# Sheet_1_2021-05-21.net
KiCad netlist of a schematic drawn in Altium Designer
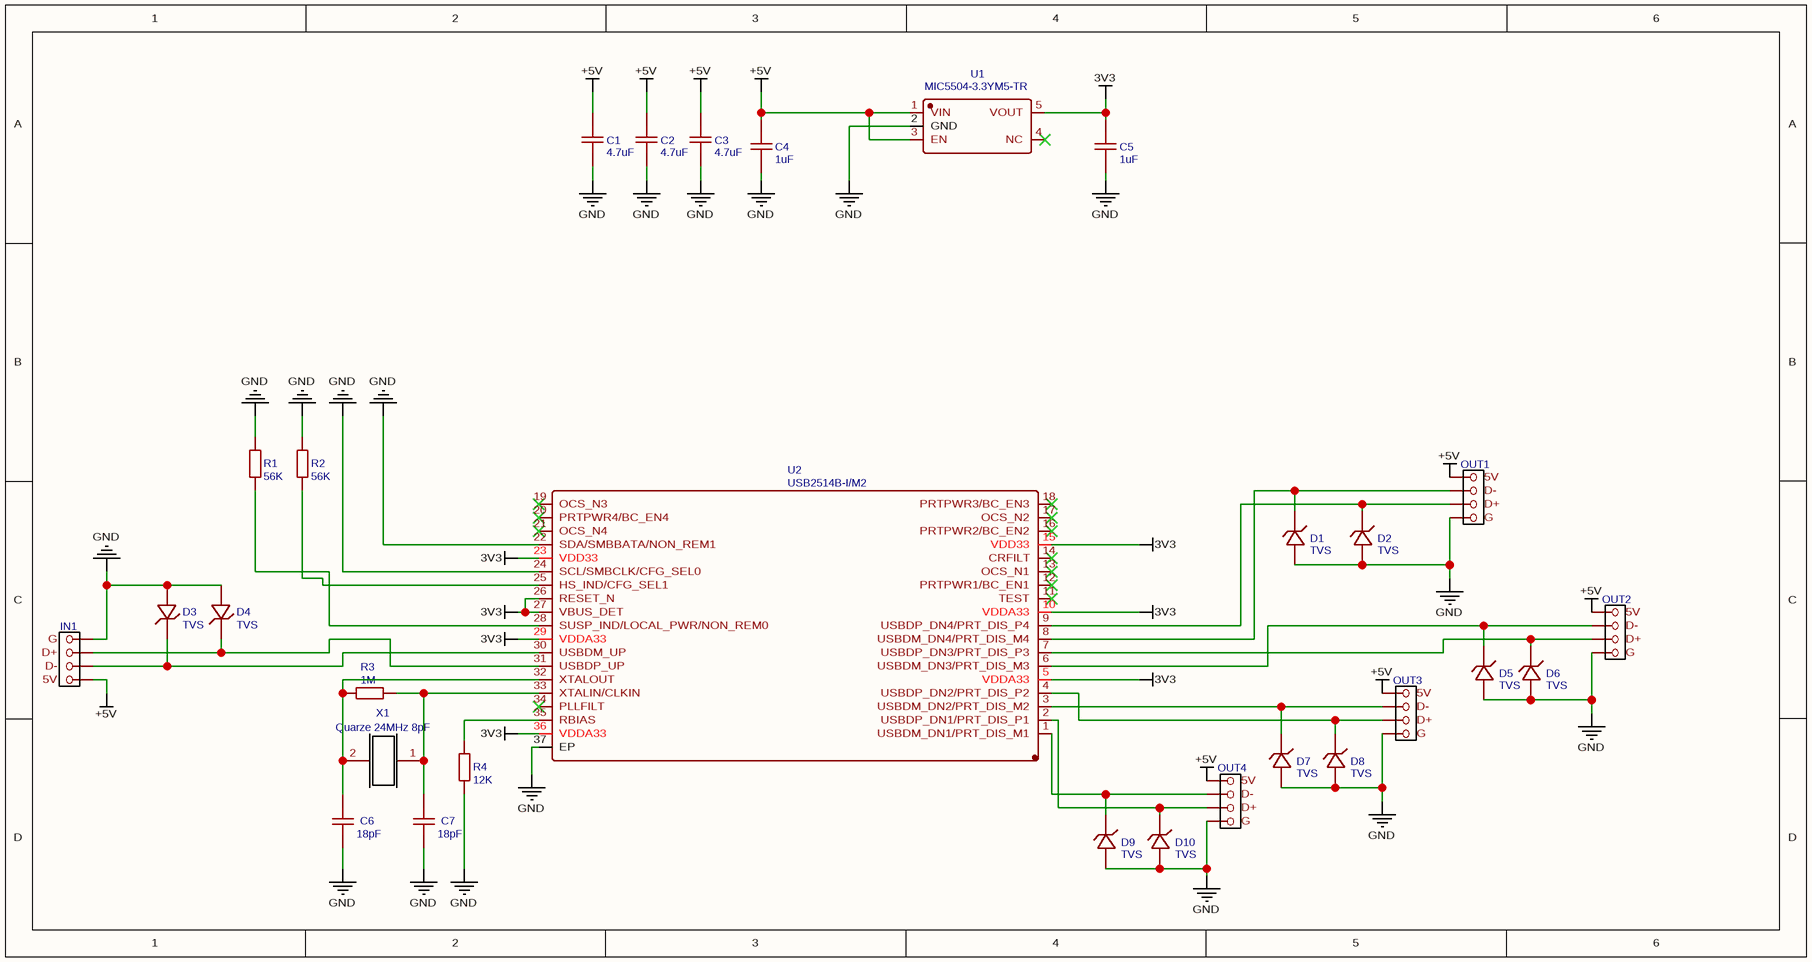
[diagram p0: Sheet_1_2021-05-21.schdoc]

(export (version "E")
  (design (tool "Eeschema 10.0.6"))
  (components
    (comp (ref "C1")
      (value "4.7uF")
      (fields (field (name "BOM_MANUFACTURER PART") "?") (field (name "BOM_SUPPLIER PART") "C1590"))
      (libsource (lib "altium-import") (part "root_3_4.7uF_"))
    )
    (comp (ref "C2")
      (value "4.7uF")
      (fields (field (name "BOM_MANUFACTURER PART") "?") (field (name "BOM_SUPPLIER PART") "C1590"))
      (libsource (lib "altium-import") (part "root_3_4.7uF_"))
    )
    (comp (ref "C3")
      (value "4.7uF")
      (fields (field (name "BOM_MANUFACTURER PART") "?") (field (name "BOM_SUPPLIER PART") "C1590"))
      (libsource (lib "altium-import") (part "root_3_4.7uF_"))
    )
    (comp (ref "C4")
      (value "1uF")
      (fields (field (name "BOM_MANUFACTURER PART") "?") (field (name "BOM_SUPPLIER PART") "C1590"))
      (libsource (lib "altium-import") (part "root_3_1uF_"))
    )
    (comp (ref "C5")
      (value "1uF")
      (fields (field (name "BOM_MANUFACTURER PART") "?") (field (name "BOM_SUPPLIER PART") "C1590"))
      (libsource (lib "altium-import") (part "root_3_1uF_"))
    )
    (comp (ref "C6")
      (value "18pF")
      (fields (field (name "BOM_MANUFACTURER PART") "?") (field (name "BOM_SUPPLIER PART") "C1590"))
      (libsource (lib "altium-import") (part "root_1_18pF_"))
    )
    (comp (ref "C7")
      (value "18pF")
      (fields (field (name "BOM_MANUFACTURER PART") "?") (field (name "BOM_SUPPLIER PART") "C1590"))
      (libsource (lib "altium-import") (part "root_1_18pF_"))
    )
    (comp (ref "D1")
      (value "TVS")
      (fields
        (field (name "BOM_SUPPLIER PART") "C172439")
        (field (name "BOM_MANUFACTURER PART") "LTVS16H12T5G")
        (field (name "CONTRIBUTOR") "LCSC")
      )
      (libsource (lib "altium-import") (part "root_3_TVS_"))
    )
    (comp (ref "D2")
      (value "TVS")
      (fields
        (field (name "BOM_SUPPLIER PART") "C172439")
        (field (name "BOM_MANUFACTURER PART") "LTVS16H12T5G")
        (field (name "CONTRIBUTOR") "LCSC")
      )
      (libsource (lib "altium-import") (part "root_3_TVS_"))
    )
    (comp (ref "D3")
      (value "TVS")
      (fields
        (field (name "BOM_SUPPLIER PART") "C172439")
        (field (name "BOM_MANUFACTURER PART") "LTVS16H12T5G")
        (field (name "CONTRIBUTOR") "LCSC")
      )
      (libsource (lib "altium-import") (part "root_1_TVS_"))
    )
    (comp (ref "D4")
      (value "TVS")
      (fields
        (field (name "BOM_SUPPLIER PART") "C172439")
        (field (name "BOM_MANUFACTURER PART") "LTVS16H12T5G")
        (field (name "CONTRIBUTOR") "LCSC")
      )
      (libsource (lib "altium-import") (part "root_1_TVS_"))
    )
    (comp (ref "D5")
      (value "TVS")
      (fields
        (field (name "BOM_SUPPLIER PART") "C172439")
        (field (name "BOM_MANUFACTURER PART") "LTVS16H12T5G")
        (field (name "CONTRIBUTOR") "LCSC")
      )
      (libsource (lib "altium-import") (part "root_3_TVS_"))
    )
    (comp (ref "D6")
      (value "TVS")
      (fields
        (field (name "BOM_SUPPLIER PART") "C172439")
        (field (name "BOM_MANUFACTURER PART") "LTVS16H12T5G")
        (field (name "CONTRIBUTOR") "LCSC")
      )
      (libsource (lib "altium-import") (part "root_3_TVS_"))
    )
    (comp (ref "D7")
      (value "TVS")
      (fields
        (field (name "BOM_SUPPLIER PART") "C172439")
        (field (name "BOM_MANUFACTURER PART") "LTVS16H12T5G")
        (field (name "CONTRIBUTOR") "LCSC")
      )
      (libsource (lib "altium-import") (part "root_3_TVS_"))
    )
    (comp (ref "D8")
      (value "TVS")
      (fields
        (field (name "BOM_SUPPLIER PART") "C172439")
        (field (name "BOM_MANUFACTURER PART") "LTVS16H12T5G")
        (field (name "CONTRIBUTOR") "LCSC")
      )
      (libsource (lib "altium-import") (part "root_3_TVS_"))
    )
    (comp (ref "D9")
      (value "TVS")
      (fields
        (field (name "BOM_SUPPLIER PART") "C172439")
        (field (name "BOM_MANUFACTURER PART") "LTVS16H12T5G")
        (field (name "CONTRIBUTOR") "LCSC")
      )
      (libsource (lib "altium-import") (part "root_3_TVS_"))
    )
    (comp (ref "D10")
      (value "TVS")
      (fields
        (field (name "BOM_SUPPLIER PART") "C172439")
        (field (name "BOM_MANUFACTURER PART") "LTVS16H12T5G")
        (field (name "CONTRIBUTOR") "LCSC")
      )
      (libsource (lib "altium-import") (part "root_3_TVS_"))
    )
    (comp (ref "IN1")
      (value "EXT-JST")
      (fields (field (name "BOM_MANUFACTURER PART") "XH-4A") (field (name "CONTRIBUTOR") "oliver.mike"))
      (libsource (lib "altium-import") (part "root_1_EXT-JST_"))
    )
    (comp (ref "OUT1")
      (value "EXT-JST")
      (fields (field (name "BOM_MANUFACTURER PART") "XH-4A") (field (name "CONTRIBUTOR") "oliver.mike"))
      (libsource (lib "altium-import") (part "root_3_EXT-JST_"))
    )
    (comp (ref "OUT2")
      (value "EXT-JST")
      (fields (field (name "BOM_MANUFACTURER PART") "XH-4A") (field (name "CONTRIBUTOR") "oliver.mike"))
      (libsource (lib "altium-import") (part "root_3_EXT-JST_"))
    )
    (comp (ref "OUT3")
      (value "EXT-JST")
      (fields (field (name "BOM_MANUFACTURER PART") "XH-4A") (field (name "CONTRIBUTOR") "oliver.mike"))
      (libsource (lib "altium-import") (part "root_3_EXT-JST_"))
    )
    (comp (ref "OUT4")
      (value "EXT-JST")
      (fields (field (name "BOM_MANUFACTURER PART") "XH-4A") (field (name "CONTRIBUTOR") "oliver.mike"))
      (libsource (lib "altium-import") (part "root_3_EXT-JST_"))
    )
    (comp (ref "R1")
      (value "56K")
      (fields (field (name "BOM_MANUFACTURER PART") "?") (field (name "BOM_SUPPLIER PART") "C25585"))
      (libsource (lib "altium-import") (part "root_3_56K_"))
    )
    (comp (ref "R2")
      (value "56K")
      (fields (field (name "BOM_MANUFACTURER PART") "?") (field (name "BOM_SUPPLIER PART") "C25585"))
      (libsource (lib "altium-import") (part "root_3_56K_"))
    )
    (comp (ref "R3")
      (value "1M")
      (fields (field (name "BOM_MANUFACTURER PART") "?") (field (name "BOM_SUPPLIER PART") "C25585"))
      (libsource (lib "altium-import") (part "root_0_1M_"))
    )
    (comp (ref "R4")
      (value "12K")
      (fields (field (name "BOM_MANUFACTURER PART") "?") (field (name "BOM_SUPPLIER PART") "C25585"))
      (libsource (lib "altium-import") (part "root_3_12K_"))
    )
    (comp (ref "U1")
      (value "MIC5504-3.3YM5-TR")
      (fields (field (name "BOM_SUPPLIER PART") "C88419") (field (name "CONTRIBUTOR") "LCSC"))
      (libsource (lib "altium-import") (part "root_0_MIC5504-3.3YM5-TR_"))
    )
    (comp (ref "U2")
      (value "USB2514B-I/M2")
      (fields (field (name "BOM_SUPPLIER PART") "C220679") (field (name "CONTRIBUTOR") "LCSC"))
      (libsource (lib "altium-import") (part "root_2_USB2514B-I/M2_"))
    )
    (comp (ref "X1")
      (value "Quarze 24MHz 8pF")
      (fields
        (field (name "BOM_MANUFACTURER PART") "ABM10W-24.0000MHZ-8-D1X-T3")
        (field (name "BOM_SUPPLIER PART") "815-10W24-8D1XT")
        (field (name "CONTRIBUTOR") "lalufani")
      )
      (libsource (lib "altium-import") (part "root_2_Quarze 24MHz 8pF_"))
    )
  )
  (nets
    (net (code "1") (name "+5V") (class "Default")
      (node (ref "C1") (pin "1") (pinfunction "1_1") (pintype "passive"))
      (node (ref "C2") (pin "1") (pinfunction "1_1") (pintype "passive"))
      (node (ref "C3") (pin "1") (pinfunction "1_1") (pintype "passive"))
      (node (ref "C4") (pin "1") (pinfunction "1_1") (pintype "passive"))
      (node (ref "IN1") (pin "1") (pinfunction "5V_1") (pintype "passive"))
      (node (ref "OUT1") (pin "1") (pinfunction "5V_1") (pintype "passive"))
      (node (ref "OUT2") (pin "1") (pinfunction "5V_1") (pintype "passive"))
      (node (ref "OUT3") (pin "1") (pinfunction "5V_1") (pintype "passive"))
      (node (ref "OUT4") (pin "1") (pinfunction "5V_1") (pintype "passive"))
      (node (ref "U1") (pin "1") (pinfunction "VIN_1") (pintype "passive"))
      (node (ref "U1") (pin "3") (pinfunction "EN_3") (pintype "passive"))
    )
    (net (code "2") (name "3V3") (class "Default")
      (node (ref "C5") (pin "1") (pinfunction "1_1") (pintype "passive"))
      (node (ref "U1") (pin "5") (pinfunction "VOUT_5") (pintype "passive"))
      (node (ref "U2") (pin "10") (pinfunction "VDDA33_10") (pintype "passive"))
      (node (ref "U2") (pin "15") (pinfunction "VDD33_15") (pintype "passive"))
      (node (ref "U2") (pin "23") (pinfunction "VDD33_23") (pintype "passive"))
      (node (ref "U2") (pin "26") (pinfunction "RESET_N_26") (pintype "passive"))
      (node (ref "U2") (pin "27") (pinfunction "VBUS_DET_27") (pintype "passive"))
      (node (ref "U2") (pin "29") (pinfunction "VDDA33_29") (pintype "passive"))
      (node (ref "U2") (pin "36") (pinfunction "VDDA33_36") (pintype "passive"))
      (node (ref "U2") (pin "5") (pinfunction "VDDA33_5") (pintype "passive"))
    )
    (net (code "3") (name "GND") (class "Default")
      (node (ref "C1") (pin "2") (pinfunction "2_2") (pintype "passive"))
      (node (ref "C2") (pin "2") (pinfunction "2_2") (pintype "passive"))
      (node (ref "C3") (pin "2") (pinfunction "2_2") (pintype "passive"))
      (node (ref "C4") (pin "2") (pinfunction "2_2") (pintype "passive"))
      (node (ref "C5") (pin "2") (pinfunction "2_2") (pintype "passive"))
      (node (ref "C6") (pin "1") (pinfunction "1_1") (pintype "passive"))
      (node (ref "C7") (pin "1") (pinfunction "1_1") (pintype "passive"))
      (node (ref "D1") (pin "2") (pinfunction "2_2") (pintype "passive"))
      (node (ref "D10") (pin "2") (pinfunction "2_2") (pintype "passive"))
      (node (ref "D2") (pin "2") (pinfunction "2_2") (pintype "passive"))
      (node (ref "D3") (pin "2") (pinfunction "2_2") (pintype "passive"))
      (node (ref "D4") (pin "2") (pinfunction "2_2") (pintype "passive"))
      (node (ref "D5") (pin "2") (pinfunction "2_2") (pintype "passive"))
      (node (ref "D6") (pin "2") (pinfunction "2_2") (pintype "passive"))
      (node (ref "D7") (pin "2") (pinfunction "2_2") (pintype "passive"))
      (node (ref "D8") (pin "2") (pinfunction "2_2") (pintype "passive"))
      (node (ref "D9") (pin "2") (pinfunction "2_2") (pintype "passive"))
      (node (ref "IN1") (pin "4") (pinfunction "G_4") (pintype "passive"))
      (node (ref "OUT1") (pin "4") (pinfunction "G_4") (pintype "passive"))
      (node (ref "OUT2") (pin "4") (pinfunction "G_4") (pintype "passive"))
      (node (ref "OUT3") (pin "4") (pinfunction "G_4") (pintype "passive"))
      (node (ref "OUT4") (pin "4") (pinfunction "G_4") (pintype "passive"))
      (node (ref "R1") (pin "1") (pinfunction "1_1") (pintype "passive"))
      (node (ref "R2") (pin "1") (pinfunction "1_1") (pintype "passive"))
      (node (ref "R4") (pin "2") (pinfunction "2_2") (pintype "passive"))
      (node (ref "U1") (pin "2") (pinfunction "GND_2") (pintype "passive"))
      (node (ref "U2") (pin "22") (pinfunction "SDA/SMBBATA/NON_REM1_22") (pintype "passive"))
      (node (ref "U2") (pin "24") (pinfunction "SCL/SMBCLK/CFG_SEL0_24") (pintype "passive"))
      (node (ref "U2") (pin "37") (pinfunction "EP_37") (pintype "passive"))
    )
    (net (code "4") (name "Net-(IN1-D+)") (class "Default")
      (node (ref "D4") (pin "1") (pinfunction "1_1") (pintype "passive"))
      (node (ref "IN1") (pin "3") (pinfunction "D+_3") (pintype "passive"))
      (node (ref "U2") (pin "31") (pinfunction "USBDP_UP_31") (pintype "passive"))
    )
    (net (code "5") (name "Net-(IN1-D-)") (class "Default")
      (node (ref "D3") (pin "1") (pinfunction "1_1") (pintype "passive"))
      (node (ref "IN1") (pin "2") (pinfunction "D-_2") (pintype "passive"))
      (node (ref "U2") (pin "30") (pinfunction "USBDM_UP_30") (pintype "passive"))
    )
    (net (code "6") (name "Net-(OUT1-D+)") (class "Default")
      (node (ref "D2") (pin "1") (pinfunction "1_1") (pintype "passive"))
      (node (ref "OUT1") (pin "3") (pinfunction "D+_3") (pintype "passive"))
      (node (ref "U2") (pin "9") (pinfunction "USBDP_DN4/PRT_DIS_P4_9") (pintype "passive"))
    )
    (net (code "7") (name "Net-(OUT1-D-)") (class "Default")
      (node (ref "D1") (pin "1") (pinfunction "1_1") (pintype "passive"))
      (node (ref "OUT1") (pin "2") (pinfunction "D-_2") (pintype "passive"))
      (node (ref "U2") (pin "8") (pinfunction "USBDM_DN4/PRT_DIS_M4_8") (pintype "passive"))
    )
    (net (code "8") (name "Net-(OUT2-D+)") (class "Default")
      (node (ref "D6") (pin "1") (pinfunction "1_1") (pintype "passive"))
      (node (ref "OUT2") (pin "3") (pinfunction "D+_3") (pintype "passive"))
      (node (ref "U2") (pin "7") (pinfunction "USBDP_DN3/PRT_DIS_P3_7") (pintype "passive"))
    )
    (net (code "9") (name "Net-(OUT2-D-)") (class "Default")
      (node (ref "D5") (pin "1") (pinfunction "1_1") (pintype "passive"))
      (node (ref "OUT2") (pin "2") (pinfunction "D-_2") (pintype "passive"))
      (node (ref "U2") (pin "6") (pinfunction "USBDM_DN3/PRT_DIS_M3_6") (pintype "passive"))
    )
    (net (code "10") (name "Net-(OUT3-D+)") (class "Default")
      (node (ref "D8") (pin "1") (pinfunction "1_1") (pintype "passive"))
      (node (ref "OUT3") (pin "3") (pinfunction "D+_3") (pintype "passive"))
      (node (ref "U2") (pin "4") (pinfunction "USBDP_DN2/PRT_DIS_P2_4") (pintype "passive"))
    )
    (net (code "11") (name "Net-(OUT3-D-)") (class "Default")
      (node (ref "D7") (pin "1") (pinfunction "1_1") (pintype "passive"))
      (node (ref "OUT3") (pin "2") (pinfunction "D-_2") (pintype "passive"))
      (node (ref "U2") (pin "3") (pinfunction "USBDM_DN2/PRT_DIS_M2_3") (pintype "passive"))
    )
    (net (code "12") (name "Net-(OUT4-D+)") (class "Default")
      (node (ref "D10") (pin "1") (pinfunction "1_1") (pintype "passive"))
      (node (ref "OUT4") (pin "3") (pinfunction "D+_3") (pintype "passive"))
      (node (ref "U2") (pin "2") (pinfunction "USBDP_DN1/PRT_DIS_P1_2") (pintype "passive"))
    )
    (net (code "13") (name "Net-(OUT4-D-)") (class "Default")
      (node (ref "D9") (pin "1") (pinfunction "1_1") (pintype "passive"))
      (node (ref "OUT4") (pin "2") (pinfunction "D-_2") (pintype "passive"))
      (node (ref "U2") (pin "1") (pinfunction "USBDM_DN1/PRT_DIS_M1_1") (pintype "passive"))
    )
    (net (code "14") (name "Net-(U2-HS_IND{slash}CFG_SEL1)") (class "Default")
      (node (ref "R2") (pin "2") (pinfunction "2_2") (pintype "passive"))
      (node (ref "U2") (pin "25") (pinfunction "HS_IND/CFG_SEL1_25") (pintype "passive"))
    )
    (net (code "15") (name "Net-(U2-RBIAS)") (class "Default")
      (node (ref "R4") (pin "1") (pinfunction "1_1") (pintype "passive"))
      (node (ref "U2") (pin "35") (pinfunction "RBIAS_35") (pintype "passive"))
    )
    (net (code "16") (name "Net-(U2-SUSP_IND{slash}LOCAL_PWR{slash}NON_REM0)") (class "Default")
      (node (ref "R1") (pin "2") (pinfunction "2_2") (pintype "passive"))
      (node (ref "U2") (pin "28") (pinfunction "SUSP_IND/LOCAL_PWR/NON_REM0_28") (pintype "passive"))
    )
    (net (code "17") (name "Net-(U2-XTALIN{slash}CLKIN)") (class "Default")
      (node (ref "C7") (pin "2") (pinfunction "2_2") (pintype "passive"))
      (node (ref "R3") (pin "2") (pinfunction "2_2") (pintype "passive"))
      (node (ref "U2") (pin "33") (pinfunction "XTALIN/CLKIN_33") (pintype "passive"))
      (node (ref "X1") (pin "1") (pinfunction "1_1") (pintype "passive"))
    )
    (net (code "18") (name "Net-(U2-XTALOUT)") (class "Default")
      (node (ref "C6") (pin "2") (pinfunction "2_2") (pintype "passive"))
      (node (ref "R3") (pin "1") (pinfunction "1_1") (pintype "passive"))
      (node (ref "U2") (pin "32") (pinfunction "XTALOUT_32") (pintype "passive"))
      (node (ref "X1") (pin "2") (pinfunction "2_2") (pintype "passive"))
    )
    (net (code "19") (name "unconnected-(U1-NC-Pad4)") (class "Default")
      (node (ref "U1") (pin "4") (pinfunction "NC_4") (pintype "passive+no_connect"))
    )
    (net (code "20") (name "unconnected-(U2-CRFILT-Pad14)") (class "Default")
      (node (ref "U2") (pin "14") (pinfunction "CRFILT_14") (pintype "passive+no_connect"))
    )
    (net (code "21") (name "unconnected-(U2-OCS_N1-Pad13)") (class "Default")
      (node (ref "U2") (pin "13") (pinfunction "OCS_N1_13") (pintype "passive+no_connect"))
    )
    (net (code "22") (name "unconnected-(U2-OCS_N2-Pad17)") (class "Default")
      (node (ref "U2") (pin "17") (pinfunction "OCS_N2_17") (pintype "passive+no_connect"))
    )
    (net (code "23") (name "unconnected-(U2-OCS_N3-Pad19)") (class "Default")
      (node (ref "U2") (pin "19") (pinfunction "OCS_N3_19") (pintype "passive+no_connect"))
    )
    (net (code "24") (name "unconnected-(U2-OCS_N4-Pad21)") (class "Default")
      (node (ref "U2") (pin "21") (pinfunction "OCS_N4_21") (pintype "passive+no_connect"))
    )
    (net (code "25") (name "unconnected-(U2-PLLFILT-Pad34)") (class "Default")
      (node (ref "U2") (pin "34") (pinfunction "PLLFILT_34") (pintype "passive+no_connect"))
    )
    (net (code "26") (name "unconnected-(U2-PRTPWR1{slash}BC_EN1-Pad12)") (class "Default")
      (node (ref "U2") (pin "12") (pinfunction "PRTPWR1/BC_EN1_12") (pintype "passive+no_connect"))
    )
    (net (code "27") (name "unconnected-(U2-PRTPWR2{slash}BC_EN2-Pad16)") (class "Default")
      (node (ref "U2") (pin "16") (pinfunction "PRTPWR2/BC_EN2_16") (pintype "passive+no_connect"))
    )
    (net (code "28") (name "unconnected-(U2-PRTPWR3{slash}BC_EN3-Pad18)") (class "Default")
      (node (ref "U2") (pin "18") (pinfunction "PRTPWR3/BC_EN3_18") (pintype "passive+no_connect"))
    )
    (net (code "29") (name "unconnected-(U2-PRTPWR4{slash}BC_EN4-Pad20)") (class "Default")
      (node (ref "U2") (pin "20") (pinfunction "PRTPWR4/BC_EN4_20") (pintype "passive+no_connect"))
    )
    (net (code "30") (name "unconnected-(U2-TEST-Pad11)") (class "Default")
      (node (ref "U2") (pin "11") (pinfunction "TEST_11") (pintype "passive+no_connect"))
    )
  )
)
